# switchboard.net
KiCad netlist of a schematic drawn in EAGLE
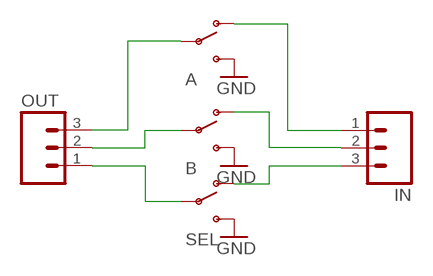
[diagram p0: schematic, sheet 1]

(export (version "E")
  (design (tool "Eeschema 10.0.6"))
  (components
    (comp (ref "A")
      (value "SWITCH-SPDTPTH")
      (footprint "eagle-import:SWITCH-SPDT")
      (libsource (lib "eagle-import") (part "SWITCH-SPDTPTH"))
    )
    (comp (ref "B")
      (value "SWITCH-SPDTPTH")
      (footprint "eagle-import:SWITCH-SPDT")
      (libsource (lib "eagle-import") (part "SWITCH-SPDTPTH"))
    )
    (comp (ref "IN")
      (value "M03LOCK")
      (footprint "eagle-import:1X03_LOCK")
      (libsource (lib "eagle-import") (part "M03LOCK"))
    )
    (comp (ref "OUT")
      (value "M03LOCK")
      (footprint "eagle-import:1X03_LOCK")
      (libsource (lib "eagle-import") (part "M03LOCK"))
    )
    (comp (ref "SEL")
      (value "SWITCH-SPDTPTH")
      (footprint "eagle-import:SWITCH-SPDT")
      (libsource (lib "eagle-import") (part "SWITCH-SPDTPTH"))
    )
  )
  (nets
    (net (code "1") (name "GND") (class "Default")
      (node (ref "A") (pin "3") (pinfunction "S_3") (pintype "passive"))
      (node (ref "B") (pin "3") (pinfunction "S_3") (pintype "passive"))
      (node (ref "SEL") (pin "3") (pinfunction "S_3") (pintype "passive"))
    )
    (net (code "2") (name "Net-(A-O)") (class "Default")
      (node (ref "A") (pin "1") (pinfunction "O_1") (pintype "passive"))
      (node (ref "IN") (pin "1") (pinfunction "1_1") (pintype "passive"))
    )
    (net (code "3") (name "Net-(A-P)") (class "Default")
      (node (ref "A") (pin "2") (pinfunction "P_2") (pintype "passive"))
      (node (ref "OUT") (pin "3") (pinfunction "3_3") (pintype "passive"))
    )
    (net (code "4") (name "Net-(B-O)") (class "Default")
      (node (ref "B") (pin "1") (pinfunction "O_1") (pintype "passive"))
      (node (ref "IN") (pin "2") (pinfunction "2_2") (pintype "passive"))
    )
    (net (code "5") (name "Net-(B-P)") (class "Default")
      (node (ref "B") (pin "2") (pinfunction "P_2") (pintype "passive"))
      (node (ref "OUT") (pin "2") (pinfunction "2_2") (pintype "passive"))
    )
    (net (code "6") (name "Net-(SEL-O)") (class "Default")
      (node (ref "IN") (pin "3") (pinfunction "3_3") (pintype "passive"))
      (node (ref "SEL") (pin "1") (pinfunction "O_1") (pintype "passive"))
    )
    (net (code "7") (name "Net-(SEL-P)") (class "Default")
      (node (ref "OUT") (pin "1") (pinfunction "1_1") (pintype "passive"))
      (node (ref "SEL") (pin "2") (pinfunction "P_2") (pintype "passive"))
    )
  )
)
